# plc_module_xs_00001_001_KQ330.net
KiCad netlist of a schematic drawn in Altium Designer
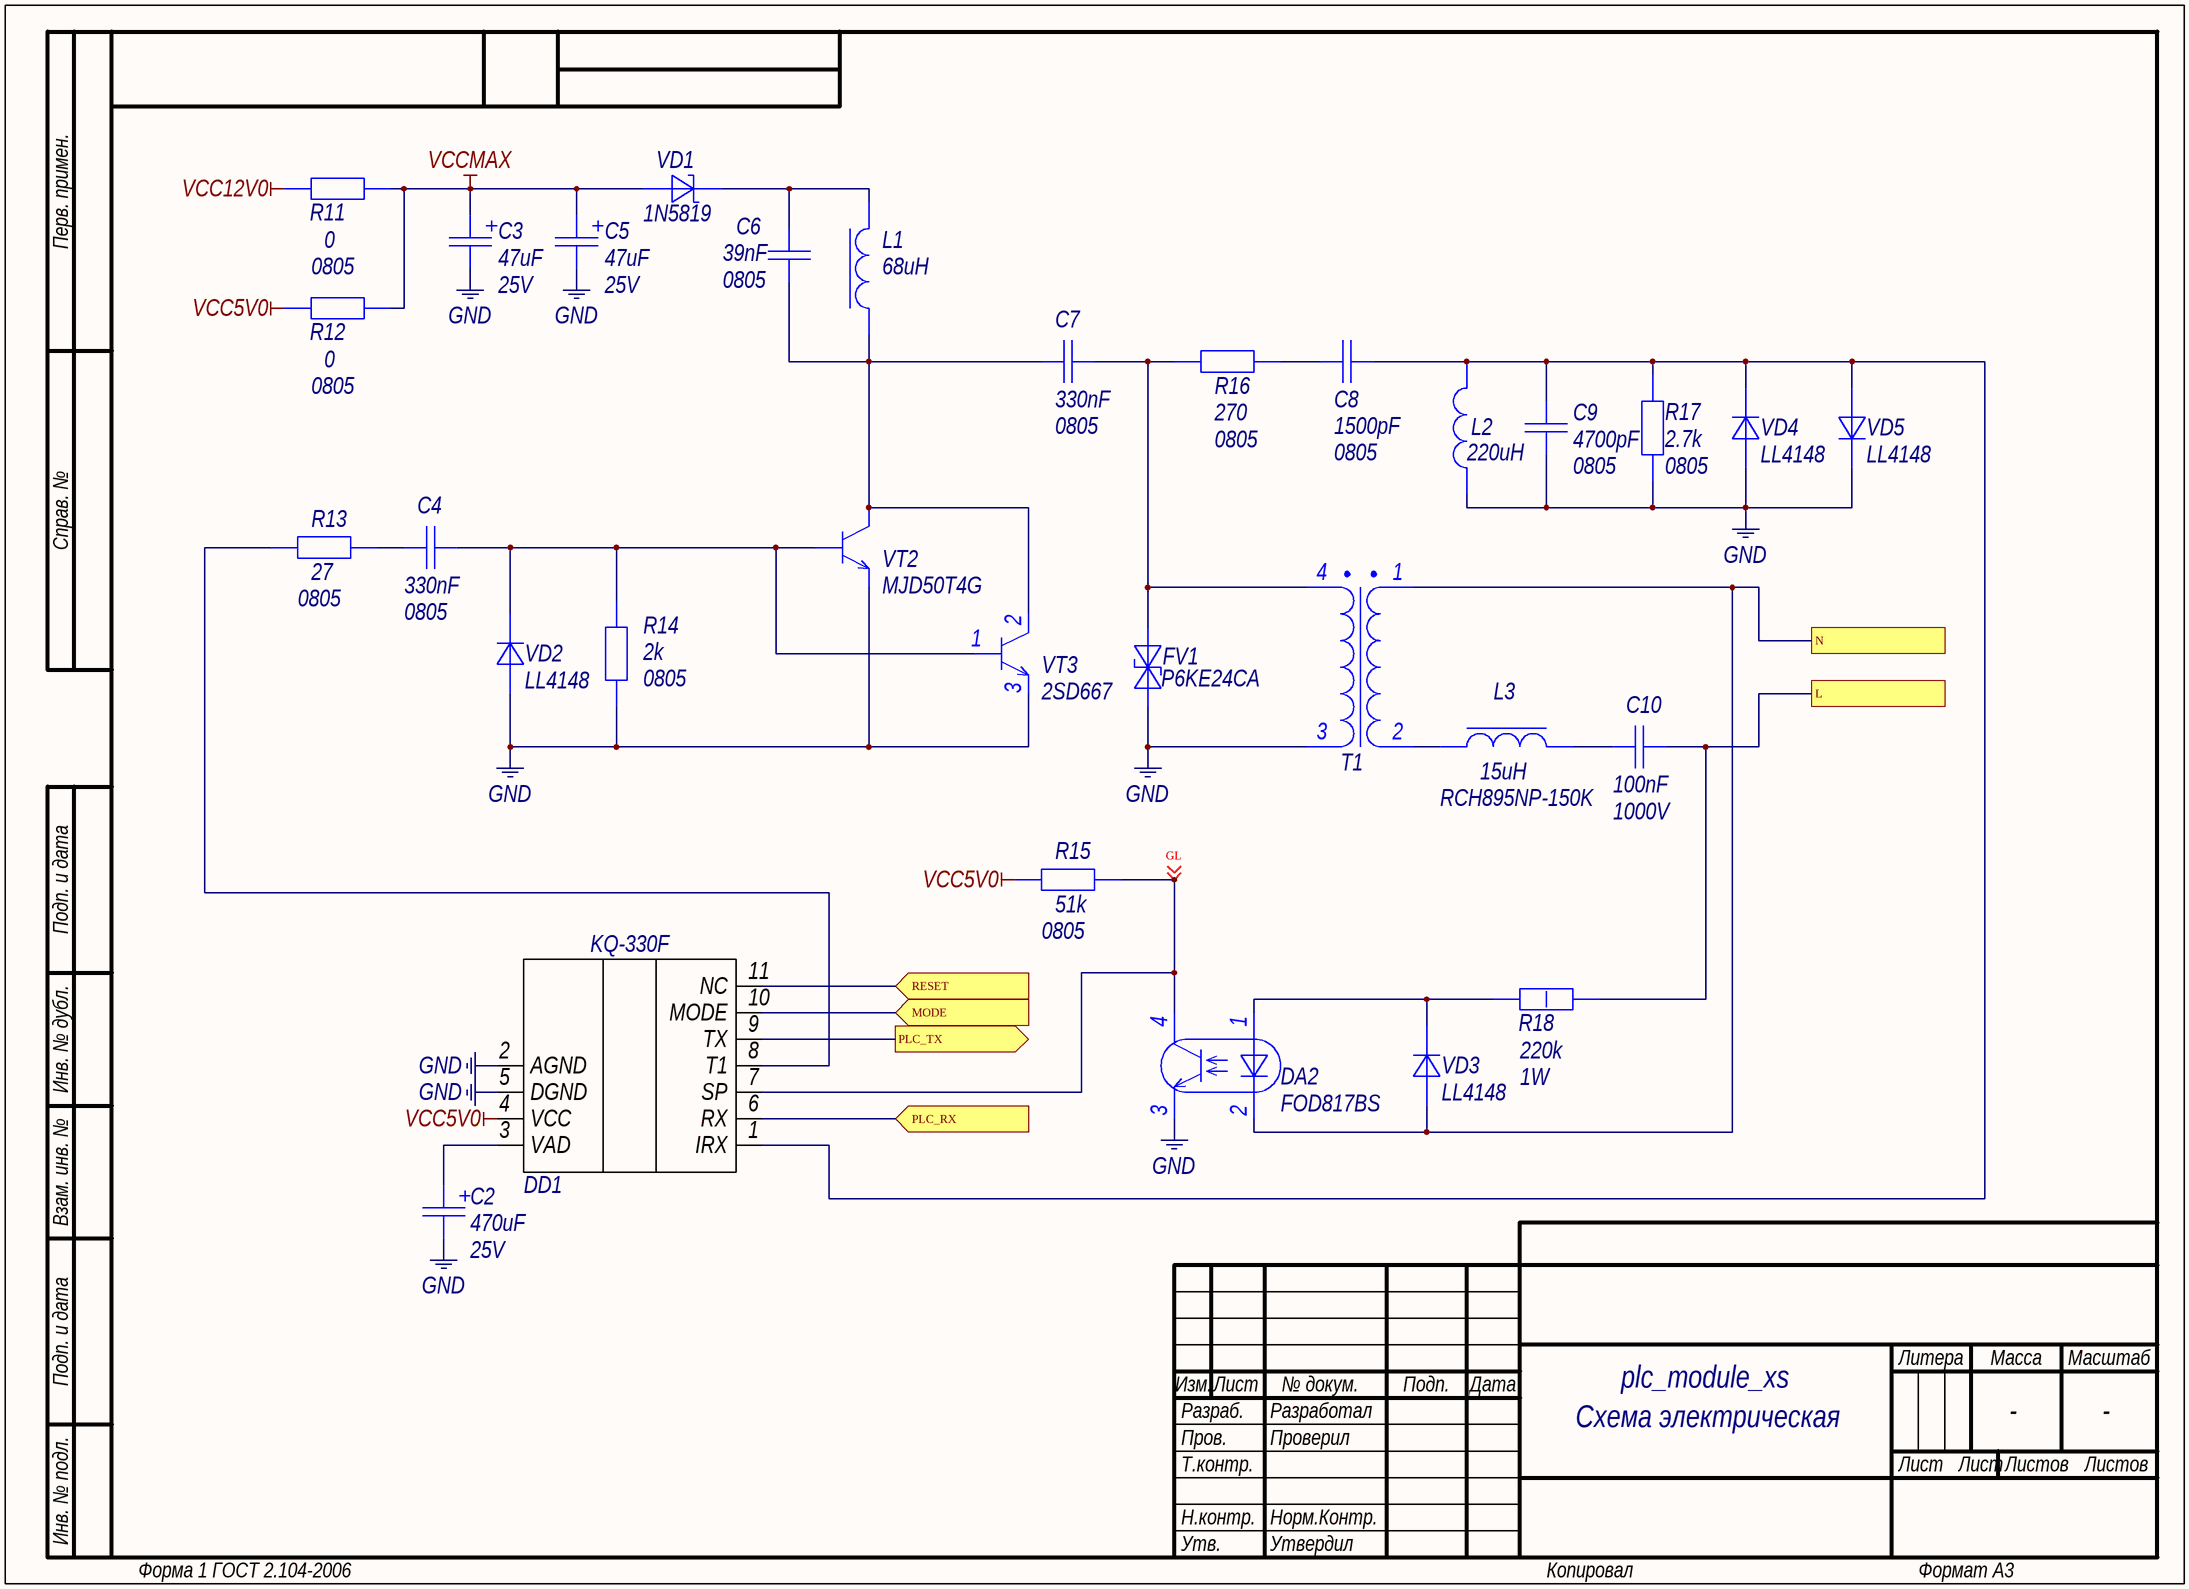
[diagram p0: plc_module_xs.00001.001_KQ330.SchDoc]

(export (version "E")
  (design (tool "Eeschema 10.0.6"))
  (components
    (comp (ref "C2")
      (value "470uF")
      (footprint "CAPAE1030X1020N")
      (fields
        (field (name "PART NUMBER") "EEEFK1E471P")
        (field (name "VOLTAGE") "25V")
        (field (name "TOLERANCE") "20%")
        (field (name "PUBLISHER") "Andrew Danich")
      )
      (libsource (lib "GOST_IMPORT_PARTS") (part "Capacitor-T"))
    )
    (comp (ref "C3")
      (value "47uF")
      (footprint "CAPAE660X540N")
      (fields
        (field (name "PART NUMBER") "EEEFK1E470P")
        (field (name "VOLTAGE") "25V")
        (field (name "TOLERANCE") "20%")
        (field (name "MANUFACTURER") "PANASONIC")
        (field (name "PUBLISHER") "Andrew Danich")
      )
      (libsource (lib "GOST_IMPORT_PARTS") (part "Capacitor-T"))
    )
    (comp (ref "C4")
      (value "330nF")
      (footprint "0805")
      (fields
        (field (name "PART NUMBER") "CC0805KKX7R9BB334")
        (field (name "VOLTAGE") "50V")
        (field (name "TOLERANCE") "±10%")
        (field (name "PUBLISHER") "Andrew Danich")
      )
      (libsource (lib "GOST_IMPORT_PARTS") (part "Capacitor"))
    )
    (comp (ref "C5")
      (value "47uF")
      (footprint "CAPAE660X540N")
      (fields
        (field (name "PART NUMBER") "EEEFK1E470P")
        (field (name "VOLTAGE") "25V")
        (field (name "TOLERANCE") "20%")
        (field (name "MANUFACTURER") "PANASONIC")
        (field (name "PUBLISHER") "Andrew Danich")
      )
      (libsource (lib "GOST_IMPORT_PARTS") (part "Capacitor-T"))
    )
    (comp (ref "C6")
      (value "39nF")
      (footprint "0805")
      (fields
        (field (name "PART NUMBER") "CC0805KRX7R9BB393")
        (field (name "VOLTAGE") "50V")
        (field (name "TOLERANCE") "±5%")
        (field (name "PUBLISHER") "Andrew Danich")
      )
      (libsource (lib "GOST_IMPORT_PARTS") (part "Capacitor"))
    )
    (comp (ref "C7")
      (value "330nF")
      (footprint "0805")
      (fields
        (field (name "PART NUMBER") "CC0805KKX7R9BB334")
        (field (name "VOLTAGE") "50V")
        (field (name "TOLERANCE") "±10%")
        (field (name "PUBLISHER") "Andrew Danich")
      )
      (libsource (lib "GOST_IMPORT_PARTS") (part "Capacitor"))
    )
    (comp (ref "C8")
      (value "1500pF")
      (footprint "0805")
      (fields
        (field (name "PART NUMBER") "CC0805JRNPO9BN152")
        (field (name "VOLTAGE") "50V")
        (field (name "TOLERANCE") "±5%")
        (field (name "PUBLISHER") "Andrew Danich")
      )
      (libsource (lib "GOST_IMPORT_PARTS") (part "Capacitor"))
    )
    (comp (ref "C9")
      (value "4700pF")
      (footprint "0805")
      (fields
        (field (name "PART NUMBER") "CC0805JKNPO9BN472")
        (field (name "VOLTAGE") "50V")
        (field (name "TOLERANCE") "±5%")
        (field (name "PUBLISHER") "Andrew Danich")
      )
      (libsource (lib "GOST_IMPORT_PARTS") (part "Capacitor"))
    )
    (comp (ref "C10")
      (value "100nF")
      (footprint "CAPR1500-800X1800X1500")
      (fields
        (field (name "PART NUMBER") "B32652A104J")
        (field (name "VOLTAGE") "1000V")
        (field (name "TOLERANCE") "5%")
        (field (name "MANUFACTURER") "EPCOS AG")
        (field (name "PUBLISHER") "Andrew Danich")
      )
      (libsource (lib "GOST_IMPORT_PARTS") (part "Capacitor"))
    )
    (comp (ref "DA2")
      (value "FOD817BS")
      (footprint "SMD-4")
      (fields (field (name "PUBLISHER") "Andrew Danich"))
      (libsource (lib "GOST_IMPORT_PARTS") (part "Photocoupler-4p"))
    )
    (comp (ref "DD1")
      (value "KQ-330F")
      (footprint "KQ-330F")
      (fields (field (name "MANUFACTURER") "kq100.com") (field (name "PUBLISHER") "Andrew Danich"))
      (libsource (lib "GOST_IMPORT_PARTS") (part "KQ-330F"))
    )
    (comp (ref "FV1")
      (value "P6KE24CA")
      (footprint "DO-15")
      (description "Suppressor-Bi")
      (fields (field (name "PUBLISHER") "Andrew Danich"))
      (libsource (lib "GOST_IMPORT_PARTS") (part "Suppressor-Bi"))
    )
    (comp (ref "L1")
      (value "68uH")
      (footprint "RLB0914_BOURNS")
      (fields
        (field (name "PART NUMBER") "RLB0914-680KL")
        (field (name "TOLERANCE") "10%")
        (field (name "PUBLISHER") "Andrew Danich")
      )
      (libsource (lib "GOST_IMPORT_PARTS") (part "Coil"))
    )
    (comp (ref "L2")
      (value "220uH")
      (footprint "EC24")
      (fields
        (field (name "PART NUMBER") "EC24-221K")
        (field (name "TOLERANCE") "10%")
        (field (name "PUBLISHER") "Andrew Danich")
      )
      (libsource (lib "GOST_IMPORT_PARTS") (part "EC24"))
    )
    (comp (ref "L3")
      (value "15uH")
      (footprint "RLB0914_BOURNS")
      (fields
        (field (name "PART NUMBER") "RCH895NP-150K")
        (field (name "TOLERANCE") "10%")
        (field (name "Comment") "RCH895NP-150K")
        (field (name "PUBLISHER") "Andrew Danich")
      )
      (libsource (lib "GOST_IMPORT_PARTS") (part "Coil"))
    )
    (comp (ref "R11")
      (value "0")
      (footprint "0805")
      (fields
        (field (name "PART NUMBER") "RC0805JR-070RL")
        (field (name "TOLERANCE") "±5%")
        (field (name "MANUFACTURER") "Yageo")
        (field (name "PUBLISHER") "Andrew Danich")
      )
      (libsource (lib "GOST_IMPORT_PARTS") (part "Resistor"))
    )
    (comp (ref "R12")
      (value "0")
      (footprint "0805")
      (fields
        (field (name "PART NUMBER") "RC0805JR-070RL")
        (field (name "TOLERANCE") "±5%")
        (field (name "MANUFACTURER") "Yageo")
        (field (name "PUBLISHER") "Andrew Danich")
      )
      (libsource (lib "GOST_IMPORT_PARTS") (part "Resistor"))
    )
    (comp (ref "R13")
      (value "27")
      (footprint "0805")
      (fields
        (field (name "PART NUMBER") "RC0805JR-0727RL")
        (field (name "TOLERANCE") "±5%")
        (field (name "MANUFACTURER") "Yageo")
        (field (name "PUBLISHER") "Andrew Danich")
      )
      (libsource (lib "GOST_IMPORT_PARTS") (part "Resistor"))
    )
    (comp (ref "R14")
      (value "2k")
      (footprint "0805")
      (fields
        (field (name "PART NUMBER") "RC0805JR-072KL")
        (field (name "TOLERANCE") "±5%")
        (field (name "MANUFACTURER") "Yageo")
        (field (name "PUBLISHER") "Andrew Danich")
      )
      (libsource (lib "GOST_IMPORT_PARTS") (part "Resistor"))
    )
    (comp (ref "R15")
      (value "51k")
      (footprint "0805")
      (fields
        (field (name "PART NUMBER") "RC0805JR-0751KL")
        (field (name "TOLERANCE") "±5%")
        (field (name "MANUFACTURER") "Yageo")
        (field (name "PUBLISHER") "Andrew Danich")
      )
      (libsource (lib "GOST_IMPORT_PARTS") (part "Resistor"))
    )
    (comp (ref "R16")
      (value "270")
      (footprint "0805")
      (fields
        (field (name "PART NUMBER") "RC0805JR-07270RL")
        (field (name "TOLERANCE") "±5%")
        (field (name "MANUFACTURER") "Yageo")
        (field (name "PUBLISHER") "Andrew Danich")
      )
      (libsource (lib "GOST_IMPORT_PARTS") (part "Resistor"))
    )
    (comp (ref "R17")
      (value "2.7k")
      (footprint "0805")
      (fields
        (field (name "PART NUMBER") "RC0805JR-072K7L")
        (field (name "TOLERANCE") "±5%")
        (field (name "MANUFACTURER") "Yageo")
        (field (name "PUBLISHER") "Andrew Danich")
      )
      (libsource (lib "GOST_IMPORT_PARTS") (part "Resistor"))
    )
    (comp (ref "R18")
      (value "220k")
      (footprint "RES1651-1000X390")
      (fields
        (field (name "PART NUMBER") "RSF200JB-73-220K")
        (field (name "TOLERANCE") "5%")
        (field (name "TOTAL POWER DISSIPATION") "1W")
        (field (name "PUBLISHER") "Andrew Danich")
      )
      (libsource (lib "GOST_IMPORT_PARTS") (part "Resistor_1,0W"))
    )
    (comp (ref "T1")
      (value "Coupling_Coil")
      (footprint "KQ330COIL")
      (description "Power Line Communication Coupling Transformer")
      (fields (field (name "PUBLISHER") "Viktor Klishin"))
      (libsource (lib "glight_custom_gost") (part "KQ330_Coupling_Coil"))
    )
    (comp (ref "VD1")
      (value "1N5819")
      (footprint "DO-41")
      (fields (field (name "MANUFACTURER") "ST Microelectronics") (field (name "PUBLISHER") "Andrew Danich"))
      (libsource (lib "GOST_IMPORT_PARTS") (part "Schottky"))
    )
    (comp (ref "VD2")
      (value "LL4148")
      (footprint "SOD-80")
      (fields (field (name "PUBLISHER") "Andrew Danich"))
      (libsource (lib "GOST_IMPORT_PARTS") (part "Diode"))
    )
    (comp (ref "VD3")
      (value "LL4148")
      (footprint "SOD-80")
      (fields (field (name "PUBLISHER") "Andrew Danich"))
      (libsource (lib "GOST_IMPORT_PARTS") (part "Diode"))
    )
    (comp (ref "VD4")
      (value "LL4148")
      (footprint "SOD-80")
      (fields (field (name "PUBLISHER") "Andrew Danich"))
      (libsource (lib "GOST_IMPORT_PARTS") (part "Diode"))
    )
    (comp (ref "VD5")
      (value "LL4148")
      (footprint "SOD-80")
      (fields (field (name "PUBLISHER") "Andrew Danich"))
      (libsource (lib "GOST_IMPORT_PARTS") (part "Diode"))
    )
    (comp (ref "VT2")
      (value "MJD50T4G")
      (footprint "DIODES-INC_TO-252-3L")
      (description "BJT-NPN")
      (fields (field (name "PUBLISHER") "Andrew Danich"))
      (libsource (lib "") (part "BJT-NPN_1"))
    )
    (comp (ref "VT3")
      (value "BJT-NPN")
      (footprint "TO-92-D")
      (fields
        (field (name "PART NUMBER") "2SD667")
        (field (name "MANUFACTURER") "HITACHI")
        (field (name "PUBLISHER") "Andrew Danich")
      )
      (libsource (lib "GOST_IMPORT_PARTS") (part "BJT-NPN"))
    )
  )
  (nets
    (net (code "1") (name "/L") (class "Default")
      (node (ref "C10") (pin "2") (pinfunction "2_2") (pintype "passive"))
      (node (ref "R18") (pin "2") (pinfunction "2_2") (pintype "passive"))
    )
    (net (code "2") (name "/MODE") (class "Default")
      (node (ref "DD1") (pin "10") (pinfunction "MODE_10") (pintype "passive"))
    )
    (net (code "3") (name "/N") (class "Default")
      (node (ref "DA2") (pin "2") (pinfunction "CК_2") (pintype "passive"))
      (node (ref "T1") (pin "1") (pinfunction "1_1") (pintype "passive"))
      (node (ref "VD3") (pin "1") (pinfunction "А_1") (pintype "passive"))
    )
    (net (code "4") (name "/PLC_RX") (class "Default")
      (node (ref "DD1") (pin "6") (pinfunction "RX_6") (pintype "passive"))
    )
    (net (code "5") (name "/PLC_TX") (class "Default")
      (node (ref "DD1") (pin "9") (pinfunction "TX_9") (pintype "passive"))
    )
    (net (code "6") (name "/RESET") (class "Default")
      (node (ref "DD1") (pin "11") (pinfunction "NC_11") (pintype "passive"))
    )
    (net (code "7") (name "GL") (class "Default")
      (node (ref "DA2") (pin "4") (pinfunction "К_4") (pintype "passive"))
      (node (ref "DD1") (pin "7") (pinfunction "SP_7") (pintype "passive"))
      (node (ref "R15") (pin "1") (pinfunction "1_1") (pintype "passive"))
    )
    (net (code "8") (name "GND") (class "Default")
      (node (ref "C2") (pin "2") (pinfunction "2_2") (pintype "passive"))
      (node (ref "C3") (pin "2") (pinfunction "2_2") (pintype "passive"))
      (node (ref "C5") (pin "2") (pinfunction "2_2") (pintype "passive"))
      (node (ref "C9") (pin "2") (pinfunction "2_2") (pintype "passive"))
      (node (ref "DA2") (pin "3") (pinfunction "Э_3") (pintype "passive"))
      (node (ref "DD1") (pin "2") (pinfunction "AGND_2") (pintype "passive"))
      (node (ref "DD1") (pin "5") (pinfunction "DGND_5") (pintype "passive"))
      (node (ref "FV1") (pin "1") (pinfunction "А_1") (pintype "passive"))
      (node (ref "L2") (pin "1") (pinfunction "1_1") (pintype "passive"))
      (node (ref "R14") (pin "1") (pinfunction "1_1") (pintype "passive"))
      (node (ref "R17") (pin "2") (pinfunction "2_2") (pintype "passive"))
      (node (ref "T1") (pin "3") (pinfunction "3_3") (pintype "passive"))
      (node (ref "VD2") (pin "1") (pinfunction "А_1") (pintype "passive"))
      (node (ref "VD4") (pin "1") (pinfunction "А_1") (pintype "passive"))
      (node (ref "VD5") (pin "2") (pinfunction "К_2") (pintype "passive"))
      (node (ref "VT2") (pin "3") (pinfunction "Э_3") (pintype "passive"))
      (node (ref "VT3") (pin "3") (pinfunction "Э_3") (pintype "passive"))
    )
    (net (code "9") (name "Net-(C4-Pad1)") (class "Default")
      (node (ref "C4") (pin "1") (pinfunction "1_1") (pintype "passive"))
      (node (ref "R13") (pin "2") (pinfunction "2_2") (pintype "passive"))
    )
    (net (code "10") (name "Net-(C8-Pad1)") (class "Default")
      (node (ref "C8") (pin "1") (pinfunction "1_1") (pintype "passive"))
      (node (ref "R16") (pin "1") (pinfunction "1_1") (pintype "passive"))
    )
    (net (code "11") (name "Net-(C10-Pad1)") (class "Default")
      (node (ref "C10") (pin "1") (pinfunction "1_1") (pintype "passive"))
      (node (ref "L3") (pin "2") (pinfunction "2_2") (pintype "passive"))
    )
    (net (code "12") (name "Net-(DA2-CА)") (class "Default")
      (node (ref "DA2") (pin "1") (pinfunction "CА_1") (pintype "passive"))
      (node (ref "R18") (pin "1") (pinfunction "1_1") (pintype "passive"))
      (node (ref "VD3") (pin "2") (pinfunction "К_2") (pintype "passive"))
    )
    (net (code "13") (name "Net-(DD1-IRX)") (class "Default")
      (node (ref "C8") (pin "2") (pinfunction "2_2") (pintype "passive"))
      (node (ref "C9") (pin "1") (pinfunction "1_1") (pintype "passive"))
      (node (ref "DD1") (pin "1") (pinfunction "IRX_1") (pintype "passive"))
      (node (ref "L2") (pin "2") (pinfunction "2_2") (pintype "passive"))
      (node (ref "R17") (pin "1") (pinfunction "1_1") (pintype "passive"))
      (node (ref "VD4") (pin "2") (pinfunction "К_2") (pintype "passive"))
      (node (ref "VD5") (pin "1") (pinfunction "А_1") (pintype "passive"))
    )
    (net (code "14") (name "Net-(DD1-T1)") (class "Default")
      (node (ref "DD1") (pin "8") (pinfunction "T1_8") (pintype "passive"))
      (node (ref "R13") (pin "1") (pinfunction "1_1") (pintype "passive"))
    )
    (net (code "15") (name "Net-(DD1-VAD)") (class "Default")
      (node (ref "C2") (pin "1") (pinfunction "1_1") (pintype "passive"))
      (node (ref "DD1") (pin "3") (pinfunction "VAD_3") (pintype "passive"))
    )
    (net (code "16") (name "Net-(FV1-К)") (class "Default")
      (node (ref "C7") (pin "2") (pinfunction "2_2") (pintype "passive"))
      (node (ref "FV1") (pin "2") (pinfunction "К_2") (pintype "passive"))
      (node (ref "R16") (pin "2") (pinfunction "2_2") (pintype "passive"))
      (node (ref "T1") (pin "4") (pinfunction "4_4") (pintype "passive"))
    )
    (net (code "17") (name "Net-(L3-Pad1)") (class "Default")
      (node (ref "L3") (pin "1") (pinfunction "1_1") (pintype "passive"))
      (node (ref "T1") (pin "2") (pinfunction "2_2") (pintype "passive"))
    )
    (net (code "18") (name "Net-(VD1-К)") (class "Default")
      (node (ref "C6") (pin "2") (pinfunction "2_2") (pintype "passive"))
      (node (ref "L1") (pin "2") (pinfunction "2_2") (pintype "passive"))
      (node (ref "VD1") (pin "1") (pinfunction "К_1") (pintype "passive"))
    )
    (net (code "19") (name "Net-(VD2-К)") (class "Default")
      (node (ref "C4") (pin "2") (pinfunction "2_2") (pintype "passive"))
      (node (ref "R14") (pin "2") (pinfunction "2_2") (pintype "passive"))
      (node (ref "VD2") (pin "2") (pinfunction "К_2") (pintype "passive"))
      (node (ref "VT2") (pin "1") (pinfunction "Б_1") (pintype "passive"))
      (node (ref "VT3") (pin "1") (pinfunction "Б_1") (pintype "passive"))
    )
    (net (code "20") (name "Net-(VT2-К)") (class "Default")
      (node (ref "C6") (pin "1") (pinfunction "1_1") (pintype "passive"))
      (node (ref "C7") (pin "1") (pinfunction "1_1") (pintype "passive"))
      (node (ref "L1") (pin "1") (pinfunction "1_1") (pintype "passive"))
      (node (ref "VT2") (pin "2") (pinfunction "К_2") (pintype "passive"))
      (node (ref "VT3") (pin "2") (pinfunction "К_2") (pintype "passive"))
    )
    (net (code "21") (name "VCC5V0") (class "Default")
      (node (ref "DD1") (pin "4") (pinfunction "VCC_4") (pintype "passive"))
      (node (ref "R12") (pin "1") (pinfunction "1_1") (pintype "passive"))
      (node (ref "R15") (pin "2") (pinfunction "2_2") (pintype "passive"))
    )
    (net (code "22") (name "VCC12V0") (class "Default")
      (node (ref "R11") (pin "1") (pinfunction "1_1") (pintype "passive"))
    )
    (net (code "23") (name "VCCMAX") (class "Default")
      (node (ref "C3") (pin "1") (pinfunction "1_1") (pintype "passive"))
      (node (ref "C5") (pin "1") (pinfunction "1_1") (pintype "passive"))
      (node (ref "R11") (pin "2") (pinfunction "2_2") (pintype "passive"))
      (node (ref "R12") (pin "2") (pinfunction "2_2") (pintype "passive"))
      (node (ref "VD1") (pin "2") (pinfunction "А_2") (pintype "passive"))
    )
  )
)
